# MOSFET_V2.net
KiCad netlist of a schematic drawn in Altium Designer
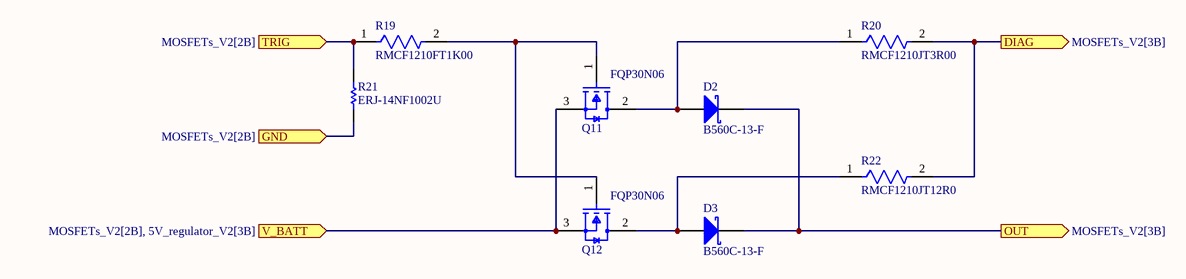
[diagram p0: MOSFET_V2.SchDoc]

(export (version "E")
  (design (tool "Eeschema 10.0.6"))
  (components
    (comp (ref "D2")
      (value "B560C-13-F")
      (footprint "DIOD-B5X0C-2_M")
      (description "Schottky Barrier Rectifier, 5 A, 60 V, -55 to 125 degC, 2-Pin SMD, RoHS, Tape and Reel")
      (fields (field (name "MANUFACTURER") "DiodesIncorporated"))
      (libsource (lib "Altium Content Vault") (part "DSKY-KA-2"))
    )
    (comp (ref "D3")
      (value "B560C-13-F")
      (footprint "DIOD-B5X0C-2_M")
      (description "Schottky Barrier Rectifier, 5 A, 60 V, -55 to 125 degC, 2-Pin SMD, RoHS, Tape and Reel")
      (fields (field (name "MANUFACTURER") "DiodesIncorporated"))
      (libsource (lib "Altium Content Vault") (part "DSKY-KA-2"))
    )
    (comp (ref "Q11")
      (value "FQP30N06")
      (footprint "FP-340AT-MFG")
      (description "MOSFET N-CH 60V 30A TO-220")
      (fields
        (field (name "OCTOPART") "https://octopart.com/fqp30n06-on+semiconductor-84328004")
        (field (name "MANUFACTURER") "ON Semiconductor")
      )
      (libsource (lib "Altium Content Vault") (part "b44c8776e10362b01251f5cff19d373"))
    )
    (comp (ref "Q12")
      (value "FQP30N06")
      (footprint "FP-340AT-MFG")
      (description "MOSFET N-CH 60V 30A TO-220")
      (fields
        (field (name "OCTOPART") "https://octopart.com/fqp30n06-on+semiconductor-84328004")
        (field (name "MANUFACTURER") "ON Semiconductor")
      )
      (libsource (lib "Altium Content Vault") (part "b44c8776e10362b01251f5cff19d373"))
    )
    (comp (ref "R19")
      (value "RMCF1210FT1K00")
      (footprint "FP-RMCF1210-IPC_A")
      (description "1kΩ ±1% 0.5W 1210 Thick Film Chip Resistor AEC-Q200 compliant")
      (fields (field (name "TOLERANCE") "1%"))
      (libsource (lib "Altium Content Vault") (part "1029c3af85768c4190bb7ad29bc67b5"))
    )
    (comp (ref "R20")
      (value "RMCF1210JT3R00")
      (footprint "FP-RMCF1210-IPC_A")
      (description "3Ω ±5% 0.5W 1210 Thick Film Chip Resistor AEC-Q200 compliant")
      (fields (field (name "TOLERANCE") "5%"))
      (libsource (lib "Altium Content Vault") (part "1029c3af85768c4190bb7ad29bc67b5"))
    )
    (comp (ref "R21")
      (value "ERJ-14NF1002U")
      (footprint "RESC3225X70X50NL20T20")
      (fields (field (name "MANUFACTURER") "Panasonic"))
      (libsource (lib "Altium Content Vault") (part "RES"))
    )
    (comp (ref "R22")
      (value "RMCF1210JT12R0")
      (footprint "FP-RMCF1210-IPC_B")
      (description "12Ω ±5% 0.5W 1210 Thick Film Chip Resistor AEC-Q200 compliant")
      (fields (field (name "TOLERANCE") "5%"))
      (libsource (lib "Altium Content Vault") (part "1029c3af85768c4190bb7ad29bc67b5"))
    )
  )
  (nets
    (net (code "1") (name "/DIAG") (class "Default")
      (node (ref "R20") (pin "2") (pinfunction "2_2") (pintype "passive"))
      (node (ref "R22") (pin "2") (pinfunction "2_2") (pintype "passive"))
    )
    (net (code "2") (name "/GND") (class "Default")
      (node (ref "R21") (pin "2") (pinfunction "2_2") (pintype "passive"))
    )
    (net (code "3") (name "/OUT") (class "Default")
      (node (ref "D2") (pin "1") (pinfunction "K_1") (pintype "passive"))
      (node (ref "D3") (pin "1") (pinfunction "K_1") (pintype "passive"))
    )
    (net (code "4") (name "/TRIG") (class "Default")
      (node (ref "R19") (pin "1") (pinfunction "1_1") (pintype "passive"))
      (node (ref "R21") (pin "1") (pinfunction "1_1") (pintype "passive"))
    )
    (net (code "5") (name "/V_BATT") (class "Default")
      (node (ref "Q11") (pin "3") (pinfunction "S_3") (pintype "passive"))
      (node (ref "Q12") (pin "3") (pinfunction "S_3") (pintype "passive"))
    )
    (net (code "6") (name "Net-(D2-A)") (class "Default")
      (node (ref "D2") (pin "2") (pinfunction "A_2") (pintype "passive"))
      (node (ref "Q11") (pin "2") (pinfunction "D_2") (pintype "passive"))
      (node (ref "R20") (pin "1") (pinfunction "1_1") (pintype "passive"))
    )
    (net (code "7") (name "Net-(D3-A)") (class "Default")
      (node (ref "D3") (pin "2") (pinfunction "A_2") (pintype "passive"))
      (node (ref "Q12") (pin "2") (pinfunction "D_2") (pintype "passive"))
      (node (ref "R22") (pin "1") (pinfunction "1_1") (pintype "passive"))
    )
    (net (code "8") (name "Net-(Q11-G)") (class "Default")
      (node (ref "Q11") (pin "1") (pinfunction "G_1") (pintype "passive"))
      (node (ref "Q12") (pin "1") (pinfunction "G_1") (pintype "passive"))
      (node (ref "R19") (pin "2") (pinfunction "2_2") (pintype "passive"))
    )
  )
)
